# 16_LMS2_RF2_Misc.net
KiCad netlist of a schematic drawn in Altium Designer
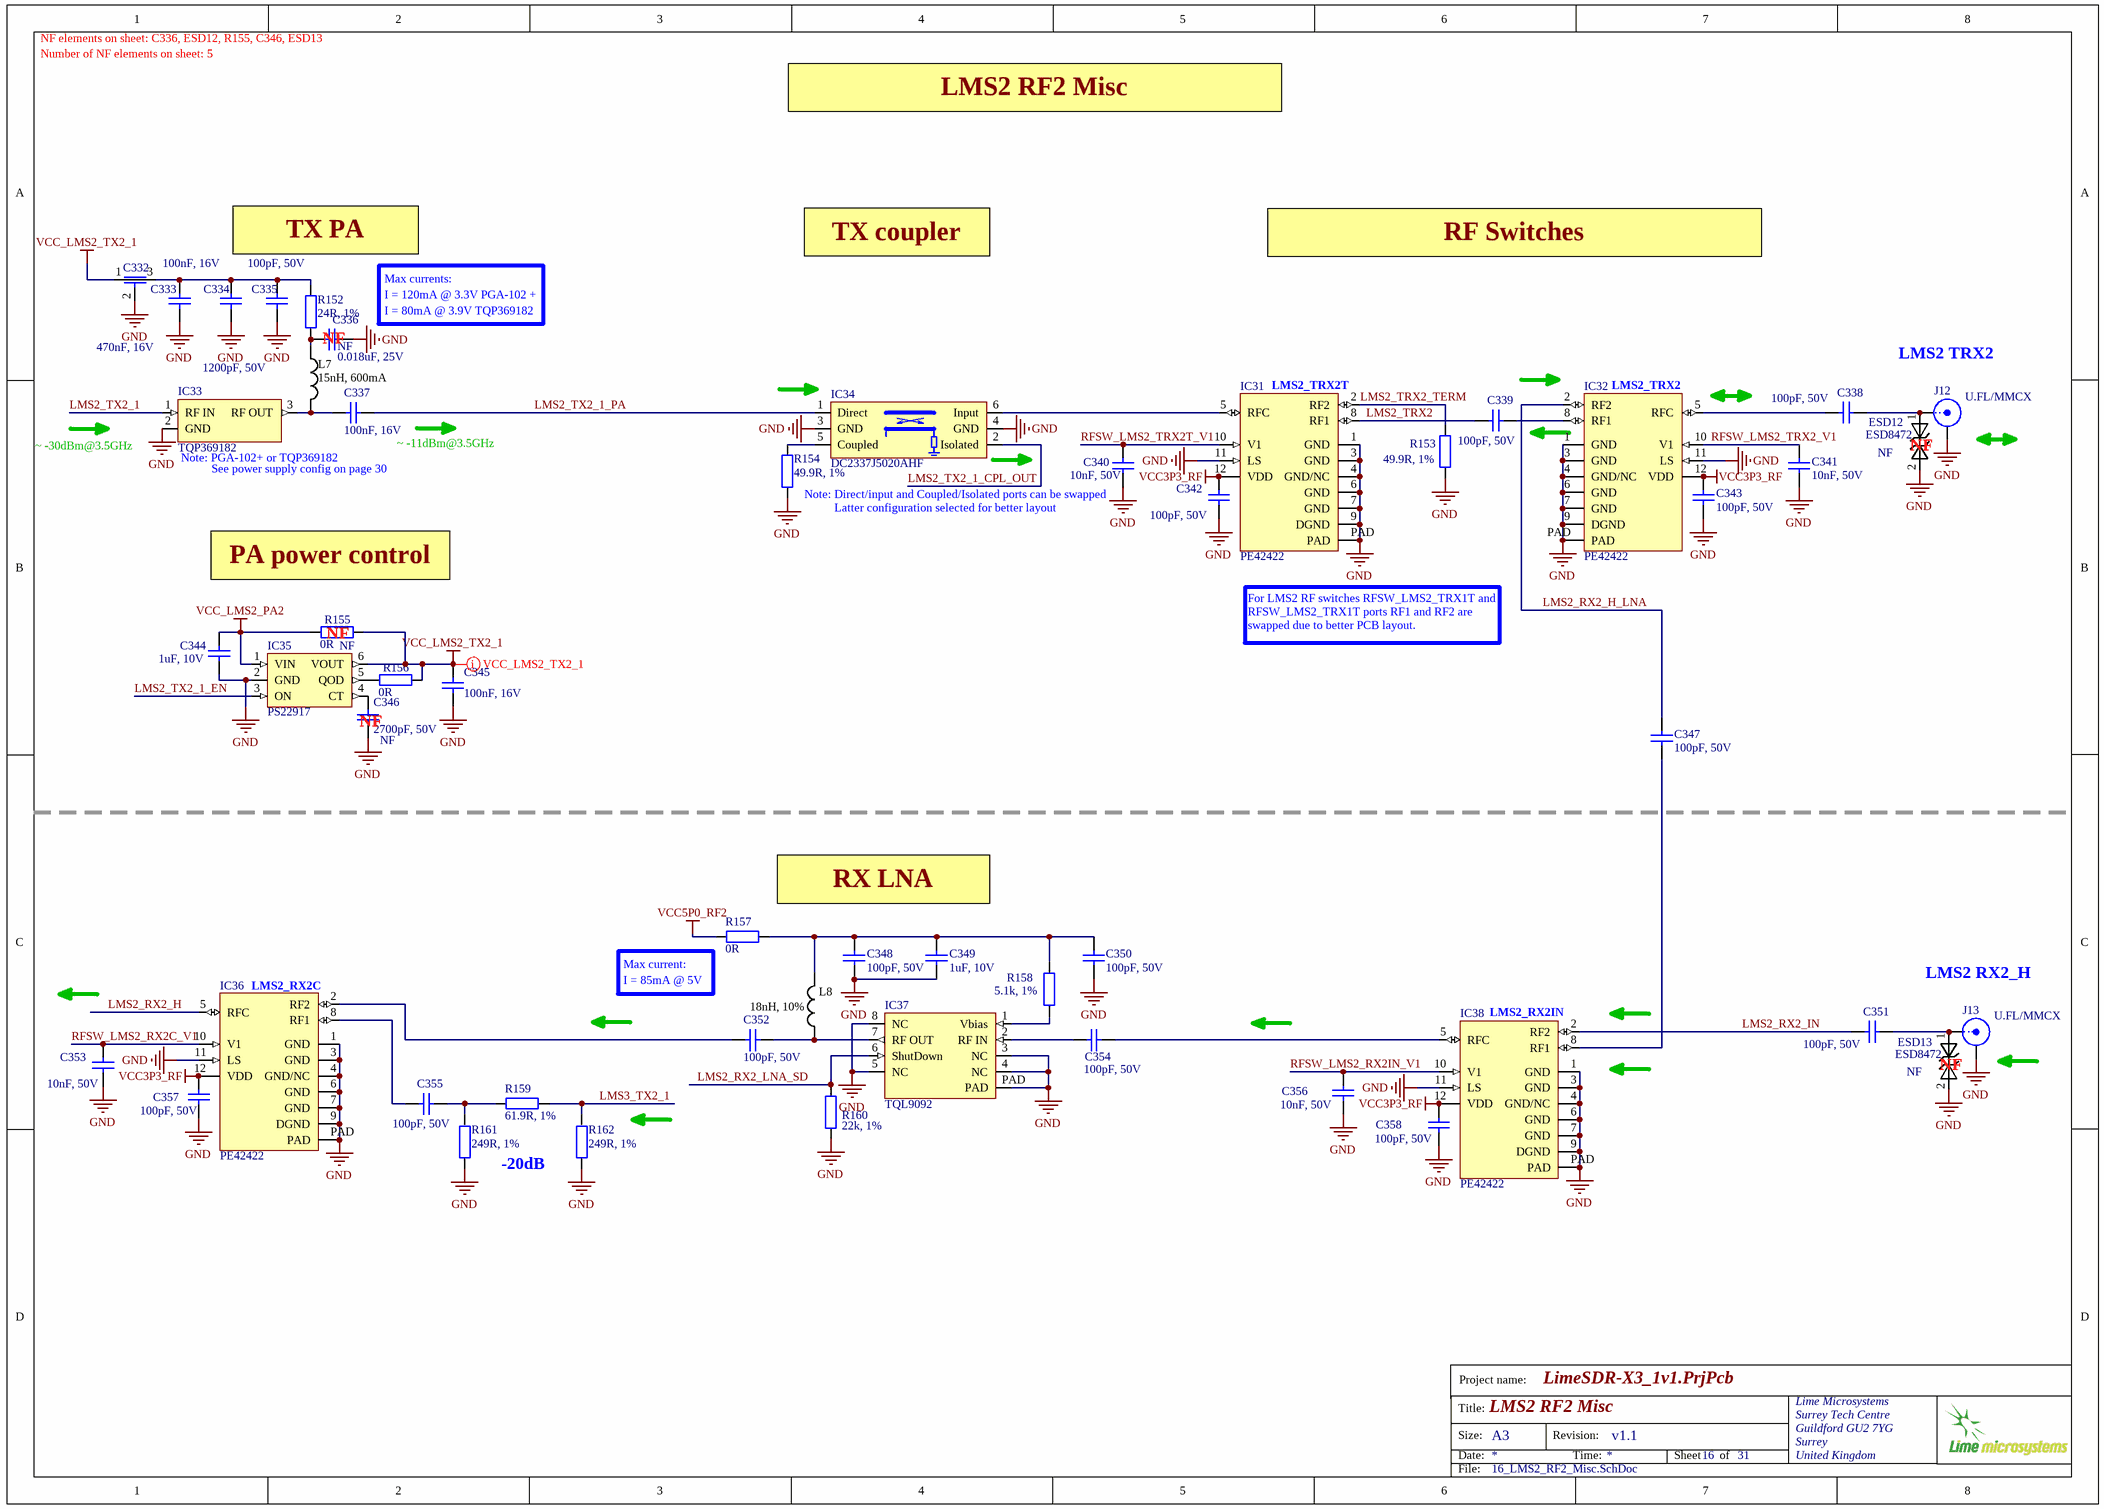
[diagram p0: 16_LMS2_RF2_Misc.SchDoc]

(export (version "E")
  (design (tool "Eeschema 10.0.6"))
  (components
    (comp (ref "C332")
      (value "470nF, 16V")
      (footprint "CAP0805_FEEDTHROUGH")
      (fields
        (field (name "MANUFACTURER") "Murata")
        (field (name "TOLERANCE") "20%")
        (field (name "VOLTAGE") "16V")
      )
      (libsource (lib "LimeMicroAltiumLib_schLib_r01") (part "Cap_feed_through"))
    )
    (comp (ref "C333")
      (value "100nF, 16V")
      (footprint "CAP0402")
      (fields (field (name "MANUFACTURER") "Murata Electronics") (field (name "TOLERANCE") "10 %"))
      (libsource (lib "") (part "Cap_0402_5"))
    )
    (comp (ref "C334")
      (value "1200pF, 50V")
      (footprint "CAP0402")
      (fields (field (name "MANUFACTURER") "Kemet") (field (name "TOLERANCE") "±5%"))
      (libsource (lib "") (part "Cap_0402_1"))
    )
    (comp (ref "C335")
      (value "100pF, 50V")
      (footprint "CAP0402")
      (fields (field (name "TOLERANCE") "±5%") (field (name "MANUFACTURER") "Yageo"))
      (libsource (lib "") (part "Cap_0402_5"))
    )
    (comp (ref "C336")
      (value "0.018uF, 25V")
      (footprint "CAP0402")
      (fields
        (field (name "ASSEMBLY INFO") "NF")
        (field (name "MANUFACTURER") "Yageo")
        (field (name "TOLERANCE") "10%")
      )
      (libsource (lib "") (part "Cap_0402_1"))
    )
    (comp (ref "C337")
      (value "100nF, 16V")
      (footprint "CAP0402")
      (fields (field (name "MANUFACTURER") "Murata Electronics") (field (name "TOLERANCE") "10 %"))
      (libsource (lib "") (part "Cap_0402_1"))
    )
    (comp (ref "C338")
      (value "100pF, 50V")
      (footprint "CAP0402")
      (fields (field (name "TOLERANCE") "±5%") (field (name "MANUFACTURER") "Yageo"))
      (libsource (lib "LimeMicroAltiumLib_schLib") (part "Cap_0402"))
    )
    (comp (ref "C339")
      (value "100pF, 50V")
      (footprint "CAP0402")
      (fields (field (name "TOLERANCE") "±5%") (field (name "MANUFACTURER") "Yageo"))
      (libsource (lib "LimeMicroAltiumLib_schLib") (part "Cap_0402"))
    )
    (comp (ref "C340")
      (value "10nF, 50V")
      (footprint "CAP0402")
      (fields
        (field (name "MANUFACTURER") "Murata Electronics North America")
        (field (name "TOLERANCE") "±10%")
      )
      (libsource (lib "") (part "Cap_0402_10"))
    )
    (comp (ref "C341")
      (value "10nF, 50V")
      (footprint "CAP0402")
      (fields
        (field (name "MANUFACTURER") "Murata Electronics North America")
        (field (name "TOLERANCE") "±10%")
      )
      (libsource (lib "") (part "Cap_0402_10"))
    )
    (comp (ref "C342")
      (value "100pF, 50V")
      (footprint "CAP0402")
      (fields (field (name "TOLERANCE") "±5%") (field (name "MANUFACTURER") "Yageo"))
      (libsource (lib "") (part "Cap_0402_7"))
    )
    (comp (ref "C343")
      (value "100pF, 50V")
      (footprint "CAP0402")
      (fields (field (name "TOLERANCE") "±5%") (field (name "MANUFACTURER") "Yageo"))
      (libsource (lib "") (part "Cap_0402_7"))
    )
    (comp (ref "C344")
      (value "1uF, 10V")
      (footprint "CAP0402")
      (fields (field (name "MANUFACTURER") "TDK"))
      (libsource (lib "") (part "Cap_0402_3"))
    )
    (comp (ref "C345")
      (value "100nF, 16V")
      (footprint "CAP0402")
      (fields (field (name "MANUFACTURER") "Murata Electronics") (field (name "TOLERANCE") "10 %"))
      (libsource (lib "") (part "Cap_0402_3"))
    )
    (comp (ref "C346")
      (value "2700pF, 50V")
      (footprint "CAP0402")
      (fields
        (field (name "ASSEMBLY INFO") "NF")
        (field (name "TOLERANCE") "±10%")
        (field (name "MANUFACTURER") "Murata Electronics North America")
      )
      (libsource (lib "") (part "Cap_0402_5"))
    )
    (comp (ref "C347")
      (value "100pF, 50V")
      (footprint "CAP0402")
      (fields (field (name "TOLERANCE") "±5%") (field (name "MANUFACTURER") "Yageo"))
      (libsource (lib "LimeMicroAltiumLib_schLib") (part "Cap_0402"))
    )
    (comp (ref "C348")
      (value "100pF, 50V")
      (footprint "CAP0402")
      (fields (field (name "TOLERANCE") "±5%") (field (name "MANUFACTURER") "Yageo"))
      (libsource (lib "") (part "Cap_0402_4"))
    )
    (comp (ref "C349")
      (value "1uF, 10V")
      (footprint "CAP0402")
      (fields (field (name "MANUFACTURER") "TDK"))
      (libsource (lib "") (part "Cap_0402_2"))
    )
    (comp (ref "C350")
      (value "100pF, 50V")
      (footprint "CAP0402")
      (fields (field (name "TOLERANCE") "±5%") (field (name "MANUFACTURER") "Yageo"))
      (libsource (lib "") (part "Cap_0402_4"))
    )
    (comp (ref "C351")
      (value "100pF, 50V")
      (footprint "CAP0402")
      (fields (field (name "TOLERANCE") "±5%") (field (name "MANUFACTURER") "Yageo"))
      (libsource (lib "LimeMicroAltiumLib_schLib") (part "Cap_0402"))
    )
    (comp (ref "C352")
      (value "100pF, 50V")
      (footprint "CAP0402")
      (fields (field (name "TOLERANCE") "±5%") (field (name "MANUFACTURER") "Yageo"))
      (libsource (lib "") (part "Cap_0402_3"))
    )
    (comp (ref "C353")
      (value "10nF, 50V")
      (footprint "CAP0402")
      (fields
        (field (name "MANUFACTURER") "Murata Electronics North America")
        (field (name "TOLERANCE") "±10%")
      )
      (libsource (lib "") (part "Cap_0402_6"))
    )
    (comp (ref "C354")
      (value "100pF, 50V")
      (footprint "CAP0402")
      (fields (field (name "TOLERANCE") "±5%") (field (name "MANUFACTURER") "Yageo"))
      (libsource (lib "") (part "Cap_0402_9"))
    )
    (comp (ref "C355")
      (value "100pF, 50V")
      (footprint "CAP0402")
      (fields (field (name "TOLERANCE") "±5%") (field (name "MANUFACTURER") "Yageo"))
      (libsource (lib "LimeMicroAltiumLib_schLib") (part "Cap_0402"))
    )
    (comp (ref "C356")
      (value "10nF, 50V")
      (footprint "CAP0402")
      (fields
        (field (name "MANUFACTURER") "Murata Electronics North America")
        (field (name "TOLERANCE") "±10%")
      )
      (libsource (lib "") (part "Cap_0402_1"))
    )
    (comp (ref "C357")
      (value "100pF, 50V")
      (footprint "CAP0402")
      (fields (field (name "TOLERANCE") "±5%") (field (name "MANUFACTURER") "Yageo"))
      (libsource (lib "") (part "Cap_0402_8"))
    )
    (comp (ref "C358")
      (value "100pF, 50V")
      (footprint "CAP0402")
      (fields (field (name "TOLERANCE") "±5%") (field (name "MANUFACTURER") "Yageo"))
      (libsource (lib "") (part "Cap_0402_1"))
    )
    (comp (ref "ESD12")
      (value "ESD8472")
      (footprint "ESD8472_X3DFN2")
      (fields (field (name "MANUFACTURER") "ON Semiconductor") (field (name "ASSEMBLY INFO") "NF"))
      (libsource (lib "") (part "ESD8472_1"))
    )
    (comp (ref "ESD13")
      (value "ESD8472")
      (footprint "ESD8472_X3DFN2")
      (fields (field (name "MANUFACTURER") "ON Semiconductor") (field (name "ASSEMBLY INFO") "NF"))
      (libsource (lib "LimeMicroAltiumLib_schLib") (part "ESD8472"))
    )
    (comp (ref "IC31")
      (value "PE42422")
      (footprint "PE42422_QFN12")
      (fields (field (name "MANUFACTURER") "Peregrine Semiconductor"))
      (libsource (lib "") (part "PE42422_1"))
    )
    (comp (ref "IC32")
      (value "PE42422")
      (footprint "PE42422_QFN12")
      (fields (field (name "MANUFACTURER") "Peregrine Semiconductor"))
      (libsource (lib "") (part "PE42422_3"))
    )
    (comp (ref "IC33")
      (value "TQP369182")
      (footprint "PGA-102+_SOT89")
      (fields (field (name "MANUFACTURER") "Qorvo"))
      (libsource (lib "LimeMicroAltiumLib_schLib_r01") (part "PGA-102+_PA"))
    )
    (comp (ref "IC34")
      (value "DC2337J5020AHF")
      (footprint "DC2337J5020AHF_ANAREN_COUPLER_0805")
      (fields (field (name "MANUFACTURER") "Anaren"))
      (libsource (lib "LimeMicroAltiumLib_schLib_r02") (part "DC2337J5020AHF_coupler"))
    )
    (comp (ref "IC35")
      (value "PS22917")
      (footprint "SOT23-6")
      (fields (field (name "MANUFACTURER") "Texas Instruments"))
      (libsource (lib "LimeMicroAltiumLib_schLib") (part "TPS22918"))
    )
    (comp (ref "IC36")
      (value "PE42422")
      (footprint "PE42422_QFN12")
      (fields (field (name "MANUFACTURER") "Peregrine Semiconductor"))
      (libsource (lib "") (part "PE42422_2"))
    )
    (comp (ref "IC37")
      (value "TQL9092")
      (footprint "TQL9092")
      (fields (field (name "MANUFACTURER") "Qorvo"))
      (libsource (lib "LimeMicroAltiumLib_schLib") (part "TQL9092"))
    )
    (comp (ref "IC38")
      (value "PE42422")
      (footprint "PE42422_QFN12")
      (fields (field (name "MANUFACTURER") "Peregrine Semiconductor"))
      (libsource (lib "LimeMicroAltiumLib_schLib") (part "PE42422"))
    )
    (comp (ref "J12")
      (value "U.FL/MMCX")
      (footprint "MMCX_UFL_conn_m")
      (description "CONN UMC RCPT STR 50 OHM SMD")
      (fields (field (name "MANUFACTURER") "Amphenol RF"))
      (libsource (lib "LimeMicroAltiumLib_schLib") (part "RF_IF_connector"))
    )
    (comp (ref "J13")
      (value "U.FL/MMCX")
      (footprint "MMCX_UFL_conn_m")
      (description "CONN UMC RCPT STR 50 OHM SMD")
      (fields (field (name "MANUFACTURER") "Amphenol RF"))
      (libsource (lib "LimeMicroAltiumLib_schLib") (part "RF_IF_connector"))
    )
    (comp (ref "L7")
      (value "15nH, 600mA")
      (footprint "RES0805")
      (fields (field (name "MANUFACTURER") "Bourns") (field (name "TOLERANCE") "5%"))
      (libsource (lib "LimeMicroAltiumLib_schLib") (part "Inductor_0603"))
    )
    (comp (ref "L8")
      (value "18nH, 10%")
      (footprint "RES0603")
      (fields (field (name "MANUFACTURER") "Pulse Electronics Network") (field (name "TOLERANCE") "±10%"))
      (libsource (lib "LimeMicroAltiumLib_schLib") (part "Inductor"))
    )
    (comp (ref "R152")
      (value "24R, 1%")
      (footprint "RES0402")
      (fields (field (name "MANUFACTURER") "Yageo") (field (name "TOLERANCE") "1%"))
      (libsource (lib "LimeFPGAboard_schLib") (part "Res_0402"))
    )
    (comp (ref "R153")
      (value "49.9R, 1%")
      (footprint "RES0402")
      (fields
        (field (name "TOLERANCE") "±1%")
        (field (name "MANUFACTURER") "Samsung Electro-Mechanics America, Inc.")
        (field (name "MANUFACTURER PART NUMBER") "RC1005F49R9CS")
      )
      (libsource (lib "") (part "Res_0402_1"))
    )
    (comp (ref "R154")
      (value "49.9R, 1%")
      (footprint "RES0402")
      (fields
        (field (name "TOLERANCE") "±1%")
        (field (name "MANUFACTURER") "Samsung Electro-Mechanics America, Inc.")
        (field (name "MANUFACTURER PART NUMBER") "RC1005F49R9CS")
      )
      (libsource (lib "") (part "Res_0402_1"))
    )
    (comp (ref "R155")
      (value "0R")
      (footprint "RES0402")
      (fields
        (field (name "ASSEMBLY INFO") "NF")
        (field (name "MANUFACTURER") "Yageo")
        (field (name "TOLERANCE") "Jumper")
      )
      (libsource (lib "LimeMicroAltiumLib_schLib") (part "Res_0402"))
    )
    (comp (ref "R156")
      (value "0R")
      (footprint "RES0402")
      (fields (field (name "MANUFACTURER") "Yageo") (field (name "TOLERANCE") "Jumper"))
      (libsource (lib "LimeMicroAltiumLib_schLib") (part "Res_0402"))
    )
    (comp (ref "R157")
      (value "0R")
      (footprint "RES0402")
      (fields (field (name "MANUFACTURER") "Yageo") (field (name "TOLERANCE") "Jumper"))
      (libsource (lib "") (part "Res_0402_1"))
    )
    (comp (ref "R158")
      (value "5.1k, 1%")
      (footprint "RES0603")
      (fields (field (name "MANUFACTURER") "Stackpole Electronics") (field (name "TOLERANCE") "1%"))
      (libsource (lib "LimeMicroAltiumLib_schLib") (part "Res_0603"))
    )
    (comp (ref "R159")
      (value "61.9R, 1%")
      (footprint "RES0402")
      (fields (field (name "MANUFACTURER") "Yageo") (field (name "TOLERANCE") "1%"))
      (libsource (lib "LimeMicroAltiumLib_schLib") (part "Res_0402"))
    )
    (comp (ref "R160")
      (value "22k, 1%")
      (footprint "RES0402")
      (fields (field (name "MANUFACTURER") "Yageo") (field (name "TOLERANCE") "±1%"))
      (libsource (lib "LimeMicroAltiumLib_schLib") (part "Res_0402"))
    )
    (comp (ref "R161")
      (value "249R, 1%")
      (footprint "RES0402")
      (fields (field (name "MANUFACTURER") "Stackpole Electronics Inc") (field (name "TOLERANCE") "±1%"))
      (libsource (lib "LimeMicroAltiumLib_schLib") (part "Res_0402"))
    )
    (comp (ref "R162")
      (value "249R, 1%")
      (footprint "RES0402")
      (fields (field (name "MANUFACTURER") "Stackpole Electronics Inc") (field (name "TOLERANCE") "±1%"))
      (libsource (lib "LimeMicroAltiumLib_schLib") (part "Res_0402"))
    )
  )
  (nets
    (net (code "1") (name "/LMS2_RX2_H") (class "Default")
      (node (ref "IC36") (pin "5") (pinfunction "RFC_5") (pintype "bidirectional"))
    )
    (net (code "2") (name "/LMS2_RX2_H_LNA") (class "Default")
      (node (ref "C347") (pin "2") (pinfunction "2_2") (pintype "passive"))
      (node (ref "IC32") (pin "2") (pinfunction "RF2_2") (pintype "bidirectional"))
    )
    (net (code "3") (name "/LMS2_RX2_IN") (class "Default")
      (node (ref "C351") (pin "1") (pinfunction "1_1") (pintype "passive"))
      (node (ref "IC38") (pin "2") (pinfunction "RF2_2") (pintype "bidirectional"))
    )
    (net (code "4") (name "/LMS2_RX2_LNA_SD") (class "Default")
      (node (ref "IC37") (pin "6") (pinfunction "ShutDown_6") (pintype "input"))
      (node (ref "R160") (pin "2") (pinfunction "2_2") (pintype "passive"))
    )
    (net (code "5") (name "/LMS2_TRX2") (class "Default")
      (node (ref "C339") (pin "1") (pinfunction "1_1") (pintype "passive"))
      (node (ref "IC31") (pin "8") (pinfunction "RF1_8") (pintype "bidirectional"))
    )
    (net (code "6") (name "/LMS2_TRX2_TERM") (class "Default")
      (node (ref "IC31") (pin "2") (pinfunction "RF2_2") (pintype "bidirectional"))
      (node (ref "R153") (pin "1") (pinfunction "1_1") (pintype "passive"))
    )
    (net (code "7") (name "/LMS2_TX2_1") (class "Default")
      (node (ref "IC33") (pin "1") (pinfunction "RF_IN_1") (pintype "input"))
    )
    (net (code "8") (name "/LMS2_TX2_1_CPL_OUT") (class "Default")
      (node (ref "IC34") (pin "2") (pinfunction "Isolated_2") (pintype "passive"))
    )
    (net (code "9") (name "/LMS2_TX2_1_EN") (class "Default")
      (node (ref "IC35") (pin "3") (pinfunction "ON_3") (pintype "input"))
    )
    (net (code "10") (name "/LMS2_TX2_1_PA") (class "Default")
      (node (ref "C337") (pin "1") (pinfunction "1_1") (pintype "passive"))
      (node (ref "IC34") (pin "1") (pinfunction "Direct_1") (pintype "passive"))
    )
    (net (code "11") (name "/LMS3_TX2_1") (class "Default")
      (node (ref "R159") (pin "2") (pinfunction "2_2") (pintype "passive"))
      (node (ref "R162") (pin "2") (pinfunction "2_2") (pintype "passive"))
    )
    (net (code "12") (name "/RFSW_LMS2_RX2C_V1") (class "Default")
      (node (ref "C353") (pin "1") (pinfunction "1_1") (pintype "passive"))
      (node (ref "IC36") (pin "10") (pinfunction "V1_10") (pintype "input"))
    )
    (net (code "13") (name "/RFSW_LMS2_RX2IN_V1") (class "Default")
      (node (ref "C356") (pin "1") (pinfunction "1_1") (pintype "passive"))
      (node (ref "IC38") (pin "10") (pinfunction "V1_10") (pintype "input"))
    )
    (net (code "14") (name "/RFSW_LMS2_TRX2T_V1") (class "Default")
      (node (ref "C340") (pin "1") (pinfunction "1_1") (pintype "passive"))
      (node (ref "IC31") (pin "10") (pinfunction "V1_10") (pintype "input"))
    )
    (net (code "15") (name "/RFSW_LMS2_TRX2_V1") (class "Default")
      (node (ref "C341") (pin "1") (pinfunction "1_1") (pintype "passive"))
      (node (ref "IC32") (pin "10") (pinfunction "V1_10") (pintype "input"))
    )
    (net (code "16") (name "GND") (class "Default")
      (node (ref "C332") (pin "2") (pinfunction "2_2") (pintype "passive"))
      (node (ref "C333") (pin "1") (pinfunction "1_1") (pintype "passive"))
      (node (ref "C334") (pin "2") (pinfunction "2_2") (pintype "passive"))
      (node (ref "C335") (pin "2") (pinfunction "2_2") (pintype "passive"))
      (node (ref "C336") (pin "2") (pinfunction "2_2") (pintype "passive"))
      (node (ref "C340") (pin "2") (pinfunction "2_2") (pintype "passive"))
      (node (ref "C341") (pin "2") (pinfunction "2_2") (pintype "passive"))
      (node (ref "C342") (pin "1") (pinfunction "1_1") (pintype "passive"))
      (node (ref "C343") (pin "1") (pinfunction "1_1") (pintype "passive"))
      (node (ref "C344") (pin "1") (pinfunction "1_1") (pintype "passive"))
      (node (ref "C345") (pin "1") (pinfunction "1_1") (pintype "passive"))
      (node (ref "C346") (pin "2") (pinfunction "2_2") (pintype "passive"))
      (node (ref "C348") (pin "2") (pinfunction "2_2") (pintype "passive"))
      (node (ref "C349") (pin "1") (pinfunction "1_1") (pintype "passive"))
      (node (ref "C350") (pin "2") (pinfunction "2_2") (pintype "passive"))
      (node (ref "C353") (pin "2") (pinfunction "2_2") (pintype "passive"))
      (node (ref "C356") (pin "2") (pinfunction "2_2") (pintype "passive"))
      (node (ref "C357") (pin "1") (pinfunction "1_1") (pintype "passive"))
      (node (ref "C358") (pin "1") (pinfunction "1_1") (pintype "passive"))
      (node (ref "ESD12") (pin "2") (pinfunction "2_2") (pintype "passive"))
      (node (ref "ESD13") (pin "2") (pinfunction "2_2") (pintype "passive"))
      (node (ref "IC31") (pin "1") (pinfunction "GND_1") (pintype "passive"))
      (node (ref "IC31") (pin "11") (pinfunction "LS_11") (pintype "input"))
      (node (ref "IC31") (pin "3") (pinfunction "GND_3") (pintype "passive"))
      (node (ref "IC31") (pin "4") (pinfunction "GND/NC_4") (pintype "passive"))
      (node (ref "IC31") (pin "6") (pinfunction "GND_6") (pintype "passive"))
      (node (ref "IC31") (pin "7") (pinfunction "GND_7") (pintype "passive"))
      (node (ref "IC31") (pin "9") (pinfunction "DGND_9") (pintype "passive"))
      (node (ref "IC31") (pin "PAD") (pinfunction "PAD_PAD") (pintype "passive"))
      (node (ref "IC32") (pin "1") (pinfunction "GND_1") (pintype "passive"))
      (node (ref "IC32") (pin "11") (pinfunction "LS_11") (pintype "input"))
      (node (ref "IC32") (pin "3") (pinfunction "GND_3") (pintype "passive"))
      (node (ref "IC32") (pin "4") (pinfunction "GND/NC_4") (pintype "passive"))
      (node (ref "IC32") (pin "6") (pinfunction "GND_6") (pintype "passive"))
      (node (ref "IC32") (pin "7") (pinfunction "GND_7") (pintype "passive"))
      (node (ref "IC32") (pin "9") (pinfunction "DGND_9") (pintype "passive"))
      (node (ref "IC32") (pin "PAD") (pinfunction "PAD_PAD") (pintype "passive"))
      (node (ref "IC33") (pin "2") (pinfunction "GND_2") (pintype "passive"))
      (node (ref "IC34") (pin "3") (pinfunction "GND_3") (pintype "passive"))
      (node (ref "IC34") (pin "4") (pinfunction "GND_4") (pintype "passive"))
      (node (ref "IC35") (pin "2") (pinfunction "GND_2") (pintype "passive"))
      (node (ref "IC36") (pin "1") (pinfunction "GND_1") (pintype "passive"))
      (node (ref "IC36") (pin "11") (pinfunction "LS_11") (pintype "input"))
      (node (ref "IC36") (pin "3") (pinfunction "GND_3") (pintype "passive"))
      (node (ref "IC36") (pin "4") (pinfunction "GND/NC_4") (pintype "passive"))
      (node (ref "IC36") (pin "6") (pinfunction "GND_6") (pintype "passive"))
      (node (ref "IC36") (pin "7") (pinfunction "GND_7") (pintype "passive"))
      (node (ref "IC36") (pin "9") (pinfunction "DGND_9") (pintype "passive"))
      (node (ref "IC36") (pin "PAD") (pinfunction "PAD_PAD") (pintype "passive"))
      (node (ref "IC37") (pin "3") (pinfunction "NC_3") (pintype "passive"))
      (node (ref "IC37") (pin "4") (pinfunction "NC_4") (pintype "passive"))
      (node (ref "IC37") (pin "5") (pinfunction "NC_5") (pintype "passive"))
      (node (ref "IC37") (pin "8") (pinfunction "NC_8") (pintype "passive"))
      (node (ref "IC37") (pin "PAD") (pinfunction "PAD_PAD") (pintype "passive"))
      (node (ref "IC38") (pin "1") (pinfunction "GND_1") (pintype "passive"))
      (node (ref "IC38") (pin "11") (pinfunction "LS_11") (pintype "input"))
      (node (ref "IC38") (pin "3") (pinfunction "GND_3") (pintype "passive"))
      (node (ref "IC38") (pin "4") (pinfunction "GND/NC_4") (pintype "passive"))
      (node (ref "IC38") (pin "6") (pinfunction "GND_6") (pintype "passive"))
      (node (ref "IC38") (pin "7") (pinfunction "GND_7") (pintype "passive"))
      (node (ref "IC38") (pin "9") (pinfunction "DGND_9") (pintype "passive"))
      (node (ref "IC38") (pin "PAD") (pinfunction "PAD_PAD") (pintype "passive"))
      (node (ref "J12") (pin "2") (pinfunction "Y_2") (pintype "passive"))
      (node (ref "J13") (pin "2") (pinfunction "Y_2") (pintype "passive"))
      (node (ref "R153") (pin "2") (pinfunction "2_2") (pintype "passive"))
      (node (ref "R154") (pin "2") (pinfunction "2_2") (pintype "passive"))
      (node (ref "R160") (pin "1") (pinfunction "1_1") (pintype "passive"))
      (node (ref "R161") (pin "1") (pinfunction "1_1") (pintype "passive"))
      (node (ref "R162") (pin "1") (pinfunction "1_1") (pintype "passive"))
    )
    (net (code "17") (name "Net-(C332-Pad3)") (class "Default")
      (node (ref "C332") (pin "3") (pinfunction "3_3") (pintype "passive"))
      (node (ref "C333") (pin "2") (pinfunction "2_2") (pintype "passive"))
      (node (ref "C334") (pin "1") (pinfunction "1_1") (pintype "passive"))
      (node (ref "C335") (pin "1") (pinfunction "1_1") (pintype "passive"))
      (node (ref "R152") (pin "1") (pinfunction "1_1") (pintype "passive"))
    )
    (net (code "18") (name "Net-(C336-Pad1)") (class "Default")
      (node (ref "C336") (pin "1") (pinfunction "1_1") (pintype "passive"))
      (node (ref "L7") (pin "1") (pinfunction "1_1") (pintype "passive"))
      (node (ref "R152") (pin "2") (pinfunction "2_2") (pintype "passive"))
    )
    (net (code "19") (name "Net-(C348-Pad1)") (class "Default")
      (node (ref "C348") (pin "1") (pinfunction "1_1") (pintype "passive"))
      (node (ref "C349") (pin "2") (pinfunction "2_2") (pintype "passive"))
      (node (ref "C350") (pin "1") (pinfunction "1_1") (pintype "passive"))
      (node (ref "L8") (pin "1") (pinfunction "1_1") (pintype "passive"))
      (node (ref "R157") (pin "2") (pinfunction "2_2") (pintype "passive"))
      (node (ref "R158") (pin "2") (pinfunction "2_2") (pintype "passive"))
    )
    (net (code "20") (name "Net-(C355-Pad1)") (class "Default")
      (node (ref "C355") (pin "1") (pinfunction "1_1") (pintype "passive"))
      (node (ref "R159") (pin "1") (pinfunction "1_1") (pintype "passive"))
      (node (ref "R161") (pin "2") (pinfunction "2_2") (pintype "passive"))
    )
    (net (code "21") (name "Net-(IC31-RFC)") (class "Default")
      (node (ref "IC31") (pin "5") (pinfunction "RFC_5") (pintype "bidirectional"))
      (node (ref "IC34") (pin "6") (pinfunction "Input_6") (pintype "passive"))
    )
    (net (code "22") (name "Net-(IC32-RF1)") (class "Default")
      (node (ref "C339") (pin "2") (pinfunction "2_2") (pintype "passive"))
      (node (ref "IC32") (pin "8") (pinfunction "RF1_8") (pintype "bidirectional"))
    )
    (net (code "23") (name "Net-(IC32-RFC)") (class "Default")
      (node (ref "C338") (pin "1") (pinfunction "1_1") (pintype "passive"))
      (node (ref "IC32") (pin "5") (pinfunction "RFC_5") (pintype "bidirectional"))
    )
    (net (code "24") (name "Net-(IC33-RF_OUT)") (class "Default")
      (node (ref "C337") (pin "2") (pinfunction "2_2") (pintype "passive"))
      (node (ref "IC33") (pin "3") (pinfunction "RF_OUT_3") (pintype "output"))
      (node (ref "L7") (pin "2") (pinfunction "2_2") (pintype "passive"))
    )
    (net (code "25") (name "Net-(IC34-Coupled)") (class "Default")
      (node (ref "IC34") (pin "5") (pinfunction "Coupled_5") (pintype "passive"))
      (node (ref "R154") (pin "1") (pinfunction "1_1") (pintype "passive"))
    )
    (net (code "26") (name "Net-(IC35-CT)") (class "Default")
      (node (ref "C346") (pin "1") (pinfunction "1_1") (pintype "passive"))
      (node (ref "IC35") (pin "4") (pinfunction "CT_4") (pintype "output"))
    )
    (net (code "27") (name "Net-(IC35-QOD)") (class "Default")
      (node (ref "IC35") (pin "5") (pinfunction "QOD_5") (pintype "output"))
      (node (ref "R156") (pin "2") (pinfunction "2_2") (pintype "passive"))
    )
    (net (code "28") (name "Net-(IC36-RF1)") (class "Default")
      (node (ref "C355") (pin "2") (pinfunction "2_2") (pintype "passive"))
      (node (ref "IC36") (pin "8") (pinfunction "RF1_8") (pintype "bidirectional"))
    )
    (net (code "29") (name "Net-(IC36-RF2)") (class "Default")
      (node (ref "C352") (pin "1") (pinfunction "1_1") (pintype "passive"))
      (node (ref "IC36") (pin "2") (pinfunction "RF2_2") (pintype "bidirectional"))
    )
    (net (code "30") (name "Net-(IC37-RF_IN)") (class "Default")
      (node (ref "C354") (pin "1") (pinfunction "1_1") (pintype "passive"))
      (node (ref "IC37") (pin "2") (pinfunction "RF_IN_2") (pintype "input"))
    )
    (net (code "31") (name "Net-(IC37-RF_OUT)") (class "Default")
      (node (ref "C352") (pin "2") (pinfunction "2_2") (pintype "passive"))
      (node (ref "IC37") (pin "7") (pinfunction "RF_OUT_7") (pintype "output"))
      (node (ref "L8") (pin "2") (pinfunction "2_2") (pintype "passive"))
    )
    (net (code "32") (name "Net-(IC37-Vbias)") (class "Default")
      (node (ref "IC37") (pin "1") (pinfunction "Vbias_1") (pintype "input"))
      (node (ref "R158") (pin "1") (pinfunction "1_1") (pintype "passive"))
    )
    (net (code "33") (name "Net-(IC38-RF1)") (class "Default")
      (node (ref "C347") (pin "1") (pinfunction "1_1") (pintype "passive"))
      (node (ref "IC38") (pin "8") (pinfunction "RF1_8") (pintype "bidirectional"))
    )
    (net (code "34") (name "Net-(IC38-RFC)") (class "Default")
      (node (ref "C354") (pin "2") (pinfunction "2_2") (pintype "passive"))
      (node (ref "IC38") (pin "5") (pinfunction "RFC_5") (pintype "bidirectional"))
    )
    (net (code "35") (name "Net-(J12-X)") (class "Default")
      (node (ref "C338") (pin "2") (pinfunction "2_2") (pintype "passive"))
      (node (ref "ESD12") (pin "1") (pinfunction "1_1") (pintype "passive"))
      (node (ref "J12") (pin "1") (pinfunction "X_1") (pintype "passive"))
    )
    (net (code "36") (name "Net-(J13-X)") (class "Default")
      (node (ref "C351") (pin "2") (pinfunction "2_2") (pintype "passive"))
      (node (ref "ESD13") (pin "1") (pinfunction "1_1") (pintype "passive"))
      (node (ref "J13") (pin "1") (pinfunction "X_1") (pintype "passive"))
    )
    (net (code "37") (name "VCC3P3_RF") (class "Default")
      (node (ref "C342") (pin "2") (pinfunction "2_2") (pintype "passive"))
      (node (ref "C343") (pin "2") (pinfunction "2_2") (pintype "passive"))
      (node (ref "C357") (pin "2") (pinfunction "2_2") (pintype "passive"))
      (node (ref "C358") (pin "2") (pinfunction "2_2") (pintype "passive"))
      (node (ref "IC31") (pin "12") (pinfunction "VDD_12") (pintype "power_in"))
      (node (ref "IC32") (pin "12") (pinfunction "VDD_12") (pintype "power_in"))
      (node (ref "IC36") (pin "12") (pinfunction "VDD_12") (pintype "power_in"))
      (node (ref "IC38") (pin "12") (pinfunction "VDD_12") (pintype "power_in"))
    )
    (net (code "38") (name "VCC5P0_RF2") (class "Default")
      (node (ref "R157") (pin "1") (pinfunction "1_1") (pintype "passive"))
    )
    (net (code "39") (name "VCC_LMS2_PA2") (class "Default")
      (node (ref "C344") (pin "2") (pinfunction "2_2") (pintype "passive"))
      (node (ref "IC35") (pin "1") (pinfunction "VIN_1") (pintype "input"))
      (node (ref "R155") (pin "2") (pinfunction "2_2") (pintype "passive"))
    )
    (net (code "40") (name "VCC_LMS2_TX2_1") (class "Default")
      (node (ref "C332") (pin "1") (pinfunction "1_1") (pintype "passive"))
      (node (ref "C345") (pin "2") (pinfunction "2_2") (pintype "passive"))
      (node (ref "IC35") (pin "6") (pinfunction "VOUT_6") (pintype "output"))
      (node (ref "R155") (pin "1") (pinfunction "1_1") (pintype "passive"))
      (node (ref "R156") (pin "1") (pinfunction "1_1") (pintype "passive"))
    )
  )
)
